# CP_Watsonville_South-Model.net
KiCad netlist of a schematic drawn in EAGLE
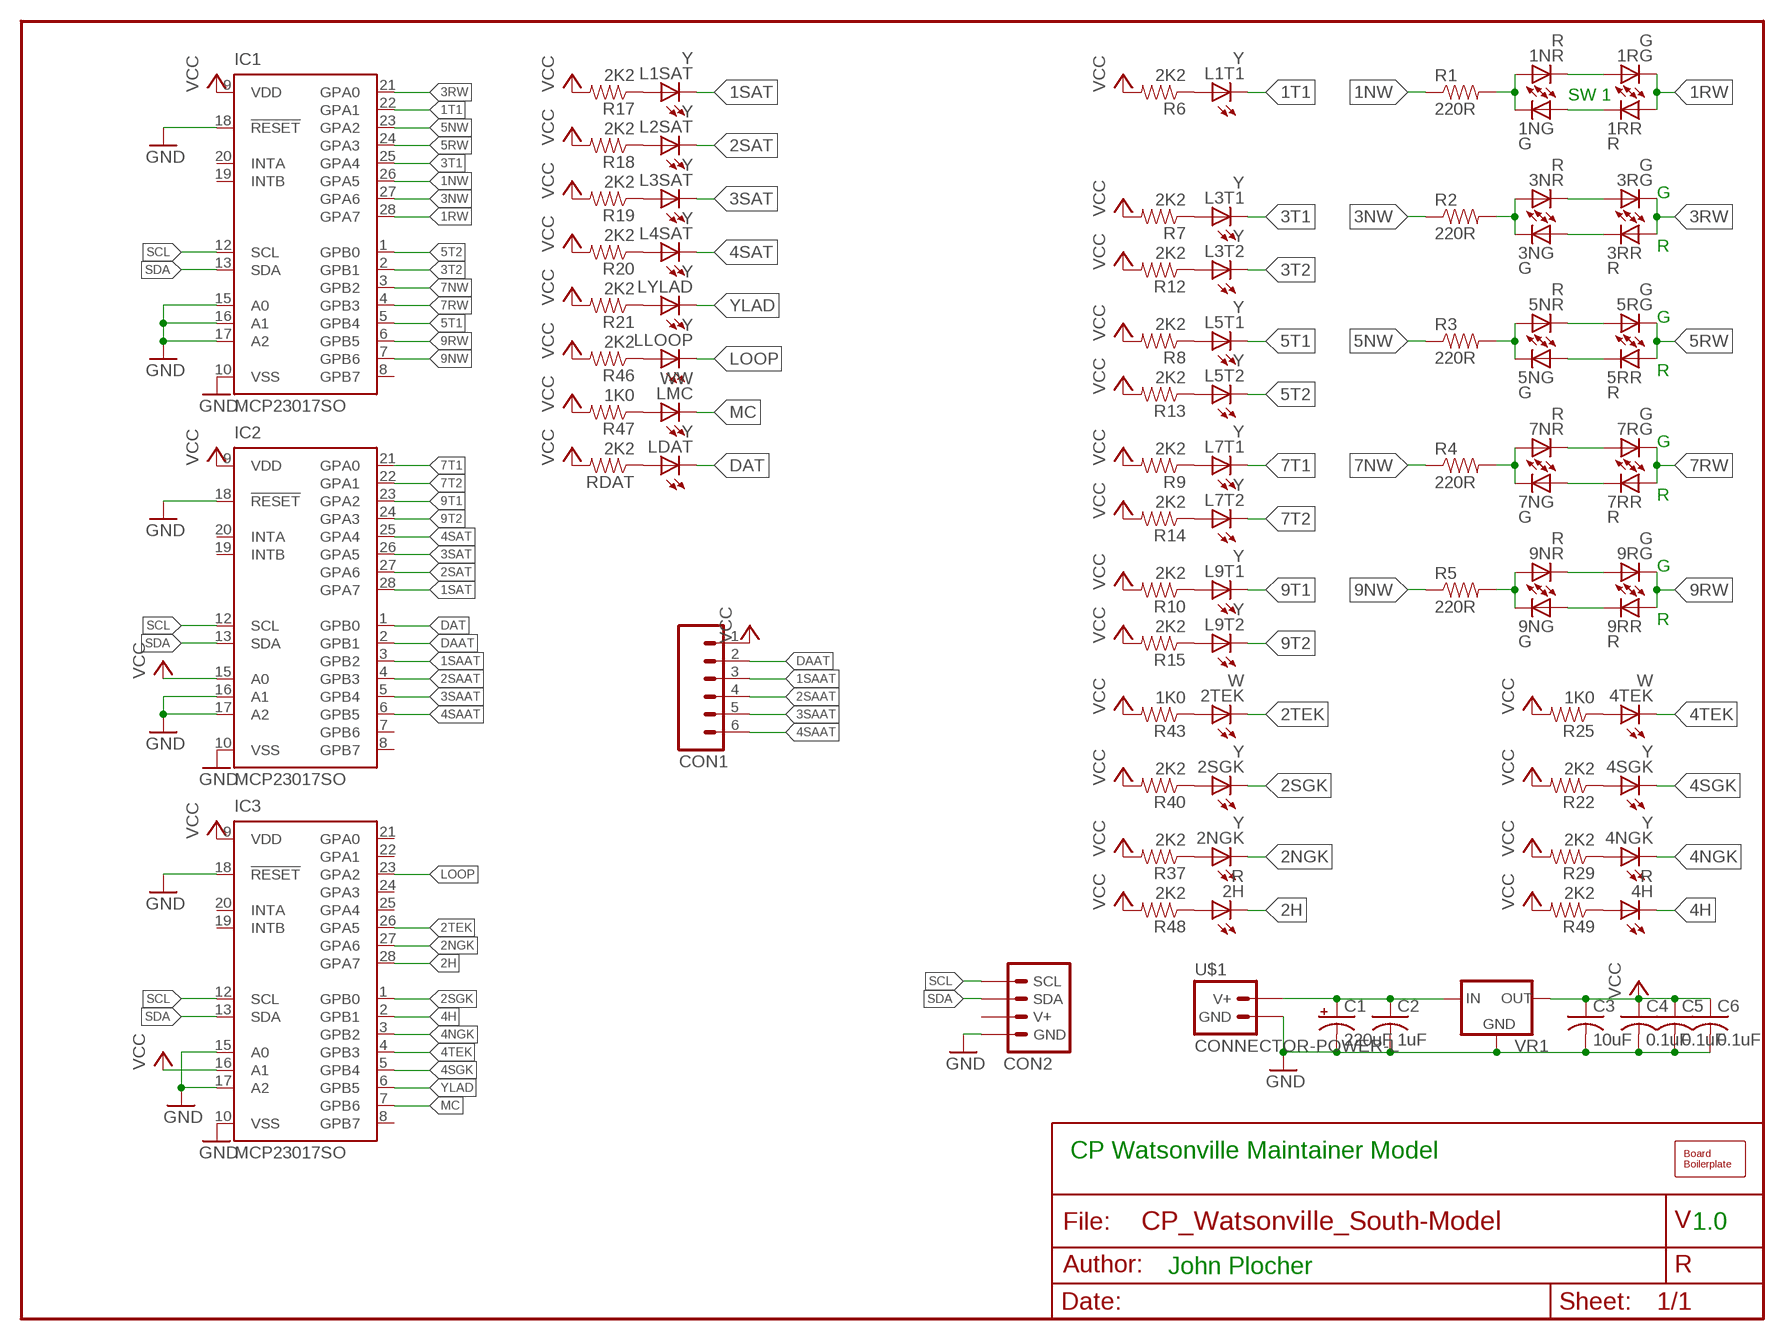
[diagram p0: schematic, sheet 1]

(export (version "E")
  (design (tool "Eeschema 10.0.6"))
  (components
    (comp (ref "1NG")
      (value "G")
      (footprint "eagle-import:0603-LED")
      (libsource (lib "eagle-import") (part "LED0603-LED"))
    )
    (comp (ref "1NR")
      (value "R")
      (footprint "eagle-import:0603-LED")
      (libsource (lib "eagle-import") (part "LED0603-LED"))
    )
    (comp (ref "1RG")
      (value "G")
      (footprint "eagle-import:0603-LED")
      (libsource (lib "eagle-import") (part "LED0603-LED"))
    )
    (comp (ref "1RR")
      (value "R")
      (footprint "eagle-import:0603-LED")
      (libsource (lib "eagle-import") (part "LED0603-LED"))
    )
    (comp (ref "2H")
      (value "R")
      (footprint "eagle-import:0603-LED")
      (libsource (lib "eagle-import") (part "LED0603-LED"))
    )
    (comp (ref "2NGK")
      (value "Y")
      (footprint "eagle-import:0603-LED")
      (libsource (lib "eagle-import") (part "LED0603-LED"))
    )
    (comp (ref "2SGK")
      (value "Y")
      (footprint "eagle-import:0603-LED")
      (libsource (lib "eagle-import") (part "LED0603-LED"))
    )
    (comp (ref "2TEK")
      (value "W")
      (footprint "eagle-import:0603-LED")
      (libsource (lib "eagle-import") (part "LED0603-LED"))
    )
    (comp (ref "3NG")
      (value "G")
      (footprint "eagle-import:0603-LED")
      (libsource (lib "eagle-import") (part "LED0603-LED"))
    )
    (comp (ref "3NR")
      (value "R")
      (footprint "eagle-import:0603-LED")
      (libsource (lib "eagle-import") (part "LED0603-LED"))
    )
    (comp (ref "3RG")
      (value "G")
      (footprint "eagle-import:0603-LED")
      (libsource (lib "eagle-import") (part "LED0603-LED"))
    )
    (comp (ref "3RR")
      (value "R")
      (footprint "eagle-import:0603-LED")
      (libsource (lib "eagle-import") (part "LED0603-LED"))
    )
    (comp (ref "4H")
      (value "R")
      (footprint "eagle-import:0603-LED")
      (libsource (lib "eagle-import") (part "LED0603-LED"))
    )
    (comp (ref "4NGK")
      (value "Y")
      (footprint "eagle-import:0603-LED")
      (libsource (lib "eagle-import") (part "LED0603-LED"))
    )
    (comp (ref "4SGK")
      (value "Y")
      (footprint "eagle-import:0603-LED")
      (libsource (lib "eagle-import") (part "LED0603-LED"))
    )
    (comp (ref "4TEK")
      (value "W")
      (footprint "eagle-import:0603-LED")
      (libsource (lib "eagle-import") (part "LED0603-LED"))
    )
    (comp (ref "5NG")
      (value "G")
      (footprint "eagle-import:0603-LED")
      (libsource (lib "eagle-import") (part "LED0603-LED"))
    )
    (comp (ref "5NR")
      (value "R")
      (footprint "eagle-import:0603-LED")
      (libsource (lib "eagle-import") (part "LED0603-LED"))
    )
    (comp (ref "5RG")
      (value "G")
      (footprint "eagle-import:0603-LED")
      (libsource (lib "eagle-import") (part "LED0603-LED"))
    )
    (comp (ref "5RR")
      (value "R")
      (footprint "eagle-import:0603-LED")
      (libsource (lib "eagle-import") (part "LED0603-LED"))
    )
    (comp (ref "7NG")
      (value "G")
      (footprint "eagle-import:0603-LED")
      (libsource (lib "eagle-import") (part "LED0603-LED"))
    )
    (comp (ref "7NR")
      (value "R")
      (footprint "eagle-import:0603-LED")
      (libsource (lib "eagle-import") (part "LED0603-LED"))
    )
    (comp (ref "7RG")
      (value "G")
      (footprint "eagle-import:0603-LED")
      (libsource (lib "eagle-import") (part "LED0603-LED"))
    )
    (comp (ref "7RR")
      (value "R")
      (footprint "eagle-import:0603-LED")
      (libsource (lib "eagle-import") (part "LED0603-LED"))
    )
    (comp (ref "9NG")
      (value "G")
      (footprint "eagle-import:0603-LED")
      (libsource (lib "eagle-import") (part "LED0603-LED"))
    )
    (comp (ref "9NR")
      (value "R")
      (footprint "eagle-import:0603-LED")
      (libsource (lib "eagle-import") (part "LED0603-LED"))
    )
    (comp (ref "9RG")
      (value "G")
      (footprint "eagle-import:0603-LED")
      (libsource (lib "eagle-import") (part "LED0603-LED"))
    )
    (comp (ref "9RR")
      (value "R")
      (footprint "eagle-import:0603-LED")
      (libsource (lib "eagle-import") (part "LED0603-LED"))
    )
    (comp (ref "BOARD1")
      (value "BOARD100X150")
      (footprint "eagle-import:BOARD-SEEED10X15")
      (libsource (lib "eagle-import") (part "BOARD100X150"))
    )
    (comp (ref "C1")
      (value "220uF")
      (footprint "eagle-import:0810-CAP")
      (libsource (lib "eagle-import") (part "CAP-POL0810"))
    )
    (comp (ref "C2")
      (value "1uF")
      (footprint "eagle-import:0603-CAP")
      (libsource (lib "eagle-import") (part "CAP0603"))
    )
    (comp (ref "C3")
      (value "10uF")
      (footprint "eagle-import:0603-CAP")
      (libsource (lib "eagle-import") (part "CAP0603"))
    )
    (comp (ref "C4")
      (value "0.1uF")
      (footprint "eagle-import:0603-CAP")
      (libsource (lib "eagle-import") (part "CAP0603"))
    )
    (comp (ref "C5")
      (value "0.1uF")
      (footprint "eagle-import:0603-CAP")
      (libsource (lib "eagle-import") (part "CAP0603"))
    )
    (comp (ref "C6")
      (value "0.1uF")
      (footprint "eagle-import:0603-CAP")
      (libsource (lib "eagle-import") (part "CAP0603"))
    )
    (comp (ref "CON1")
      (value "CONNECTOR-M06LOCK")
      (footprint "eagle-import:1X06_LOCK")
      (libsource (lib "eagle-import") (part "CONNECTOR-M06LOCK"))
    )
    (comp (ref "CON2")
      (value "CONNECTOR-I2CNOOUTLINE")
      (footprint "eagle-import:I2C-NOOUTLINE")
      (libsource (lib "eagle-import") (part "CONNECTOR-I2CNOOUTLINE"))
    )
    (comp (ref "IC1")
      (value "MCP23017SO")
      (footprint "eagle-import:SO28W")
      (fields (field (name "MF") "MICROCHIP") (field (name "MPN") "MCP23017-E/SO"))
      (libsource (lib "eagle-import") (part "MCP23017SO"))
    )
    (comp (ref "IC2")
      (value "MCP23017SO")
      (footprint "eagle-import:SO28W")
      (fields (field (name "MF") "MICROCHIP") (field (name "MPN") "MCP23017-E/SO"))
      (libsource (lib "eagle-import") (part "MCP23017SO"))
    )
    (comp (ref "IC3")
      (value "MCP23017SO")
      (footprint "eagle-import:SO28W")
      (fields (field (name "MF") "MICROCHIP") (field (name "MPN") "MCP23017-E/SO"))
      (libsource (lib "eagle-import") (part "MCP23017SO"))
    )
    (comp (ref "L1SAT")
      (value "Y")
      (footprint "eagle-import:0603-LED")
      (libsource (lib "eagle-import") (part "LED0603-LED"))
    )
    (comp (ref "L1T1")
      (value "Y")
      (footprint "eagle-import:0603-LED")
      (libsource (lib "eagle-import") (part "LED0603-LED"))
    )
    (comp (ref "L2SAT")
      (value "Y")
      (footprint "eagle-import:0603-LED")
      (libsource (lib "eagle-import") (part "LED0603-LED"))
    )
    (comp (ref "L3SAT")
      (value "Y")
      (footprint "eagle-import:0603-LED")
      (libsource (lib "eagle-import") (part "LED0603-LED"))
    )
    (comp (ref "L3T1")
      (value "Y")
      (footprint "eagle-import:0603-LED")
      (libsource (lib "eagle-import") (part "LED0603-LED"))
    )
    (comp (ref "L3T2")
      (value "Y")
      (footprint "eagle-import:0603-LED")
      (libsource (lib "eagle-import") (part "LED0603-LED"))
    )
    (comp (ref "L4SAT")
      (value "Y")
      (footprint "eagle-import:0603-LED")
      (libsource (lib "eagle-import") (part "LED0603-LED"))
    )
    (comp (ref "L5T1")
      (value "Y")
      (footprint "eagle-import:0603-LED")
      (libsource (lib "eagle-import") (part "LED0603-LED"))
    )
    (comp (ref "L5T2")
      (value "Y")
      (footprint "eagle-import:0603-LED")
      (libsource (lib "eagle-import") (part "LED0603-LED"))
    )
    (comp (ref "L7T1")
      (value "Y")
      (footprint "eagle-import:0603-LED")
      (libsource (lib "eagle-import") (part "LED0603-LED"))
    )
    (comp (ref "L7T2")
      (value "Y")
      (footprint "eagle-import:0603-LED")
      (libsource (lib "eagle-import") (part "LED0603-LED"))
    )
    (comp (ref "L9T1")
      (value "Y")
      (footprint "eagle-import:0603-LED")
      (libsource (lib "eagle-import") (part "LED0603-LED"))
    )
    (comp (ref "L9T2")
      (value "Y")
      (footprint "eagle-import:0603-LED")
      (libsource (lib "eagle-import") (part "LED0603-LED"))
    )
    (comp (ref "LDAT")
      (value "Y")
      (footprint "eagle-import:0603-LED")
      (libsource (lib "eagle-import") (part "LED0603-LED"))
    )
    (comp (ref "LLOOP")
      (value "Y")
      (footprint "eagle-import:0603-LED")
      (libsource (lib "eagle-import") (part "LED0603-LED"))
    )
    (comp (ref "LMC")
      (value "WW")
      (footprint "eagle-import:0603-LED")
      (libsource (lib "eagle-import") (part "LED0603-LED"))
    )
    (comp (ref "LYLAD")
      (value "Y")
      (footprint "eagle-import:0603-LED")
      (libsource (lib "eagle-import") (part "LED0603-LED"))
    )
    (comp (ref "R1")
      (value "220R")
      (footprint "eagle-import:0603-RES")
      (libsource (lib "eagle-import") (part "R0603-RES"))
    )
    (comp (ref "R2")
      (value "220R")
      (footprint "eagle-import:0603-RES")
      (libsource (lib "eagle-import") (part "R0603-RES"))
    )
    (comp (ref "R3")
      (value "220R")
      (footprint "eagle-import:0603-RES")
      (libsource (lib "eagle-import") (part "R0603-RES"))
    )
    (comp (ref "R4")
      (value "220R")
      (footprint "eagle-import:0603-RES")
      (libsource (lib "eagle-import") (part "R0603-RES"))
    )
    (comp (ref "R5")
      (value "220R")
      (footprint "eagle-import:0603-RES")
      (libsource (lib "eagle-import") (part "R0603-RES"))
    )
    (comp (ref "R6")
      (value "2K2")
      (footprint "eagle-import:0603-RES")
      (libsource (lib "eagle-import") (part "R0603-RES"))
    )
    (comp (ref "R7")
      (value "2K2")
      (footprint "eagle-import:0603-RES")
      (libsource (lib "eagle-import") (part "R0603-RES"))
    )
    (comp (ref "R8")
      (value "2K2")
      (footprint "eagle-import:0603-RES")
      (libsource (lib "eagle-import") (part "R0603-RES"))
    )
    (comp (ref "R9")
      (value "2K2")
      (footprint "eagle-import:0603-RES")
      (libsource (lib "eagle-import") (part "R0603-RES"))
    )
    (comp (ref "R10")
      (value "2K2")
      (footprint "eagle-import:0603-RES")
      (libsource (lib "eagle-import") (part "R0603-RES"))
    )
    (comp (ref "R12")
      (value "2K2")
      (footprint "eagle-import:0603-RES")
      (libsource (lib "eagle-import") (part "R0603-RES"))
    )
    (comp (ref "R13")
      (value "2K2")
      (footprint "eagle-import:0603-RES")
      (libsource (lib "eagle-import") (part "R0603-RES"))
    )
    (comp (ref "R14")
      (value "2K2")
      (footprint "eagle-import:0603-RES")
      (libsource (lib "eagle-import") (part "R0603-RES"))
    )
    (comp (ref "R15")
      (value "2K2")
      (footprint "eagle-import:0603-RES")
      (libsource (lib "eagle-import") (part "R0603-RES"))
    )
    (comp (ref "R17")
      (value "2K2")
      (footprint "eagle-import:0603-RES")
      (libsource (lib "eagle-import") (part "R0603-RES"))
    )
    (comp (ref "R18")
      (value "2K2")
      (footprint "eagle-import:0603-RES")
      (libsource (lib "eagle-import") (part "R0603-RES"))
    )
    (comp (ref "R19")
      (value "2K2")
      (footprint "eagle-import:0603-RES")
      (libsource (lib "eagle-import") (part "R0603-RES"))
    )
    (comp (ref "R20")
      (value "2K2")
      (footprint "eagle-import:0603-RES")
      (libsource (lib "eagle-import") (part "R0603-RES"))
    )
    (comp (ref "R21")
      (value "2K2")
      (footprint "eagle-import:0603-RES")
      (libsource (lib "eagle-import") (part "R0603-RES"))
    )
    (comp (ref "R22")
      (value "2K2")
      (footprint "eagle-import:0603-RES")
      (libsource (lib "eagle-import") (part "R0603-RES"))
    )
    (comp (ref "R25")
      (value "1K0")
      (footprint "eagle-import:0603-RES")
      (libsource (lib "eagle-import") (part "R0603-RES"))
    )
    (comp (ref "R29")
      (value "2K2")
      (footprint "eagle-import:0603-RES")
      (libsource (lib "eagle-import") (part "R0603-RES"))
    )
    (comp (ref "R37")
      (value "2K2")
      (footprint "eagle-import:0603-RES")
      (libsource (lib "eagle-import") (part "R0603-RES"))
    )
    (comp (ref "R40")
      (value "2K2")
      (footprint "eagle-import:0603-RES")
      (libsource (lib "eagle-import") (part "R0603-RES"))
    )
    (comp (ref "R43")
      (value "1K0")
      (footprint "eagle-import:0603-RES")
      (libsource (lib "eagle-import") (part "R0603-RES"))
    )
    (comp (ref "R46")
      (value "2K2")
      (footprint "eagle-import:0603-RES")
      (libsource (lib "eagle-import") (part "R0603-RES"))
    )
    (comp (ref "R47")
      (value "1K0")
      (footprint "eagle-import:0603-RES")
      (libsource (lib "eagle-import") (part "R0603-RES"))
    )
    (comp (ref "R48")
      (value "2K2")
      (footprint "eagle-import:0603-RES")
      (libsource (lib "eagle-import") (part "R0603-RES"))
    )
    (comp (ref "R49")
      (value "2K2")
      (footprint "eagle-import:0603-RES")
      (libsource (lib "eagle-import") (part "R0603-RES"))
    )
    (comp (ref "RDAT")
      (value "2K2")
      (footprint "eagle-import:0603-RES")
      (libsource (lib "eagle-import") (part "R0603-RES"))
    )
    (comp (ref "U$1")
      (value "CONNECTOR-POWER-L")
      (footprint "eagle-import:POWER-R2")
      (libsource (lib "eagle-import") (part "CONNECTOR-POWER-L"))
    )
    (comp (ref "VR1")
      (value "VREG-DPAK-5")
      (footprint "eagle-import:TO-252")
      (libsource (lib "eagle-import") (part "VREG-?-DPAK5"))
    )
  )
  (nets
    (net (code "1") (name "1NW") (class "Default")
      (node (ref "IC1") (pin "26") (pinfunction "GPA5_26") (pintype "bidirectional"))
      (node (ref "R1") (pin "1") (pinfunction "1_1") (pintype "passive"))
    )
    (net (code "2") (name "1RW") (class "Default")
      (node (ref "1RG") (pin "C") (pinfunction "C_C") (pintype "passive"))
      (node (ref "1RR") (pin "A") (pinfunction "A_A") (pintype "passive"))
      (node (ref "IC1") (pin "28") (pinfunction "GPA7_28") (pintype "bidirectional"))
    )
    (net (code "3") (name "1SAAT") (class "Default")
      (node (ref "CON1") (pin "3") (pinfunction "3_3") (pintype "passive"))
      (node (ref "IC2") (pin "3") (pinfunction "GPB2_3") (pintype "bidirectional"))
    )
    (net (code "4") (name "1SAT") (class "Default")
      (node (ref "IC2") (pin "28") (pinfunction "GPA7_28") (pintype "bidirectional"))
      (node (ref "L1SAT") (pin "C") (pinfunction "C_C") (pintype "passive"))
    )
    (net (code "5") (name "1T1") (class "Default")
      (node (ref "IC1") (pin "22") (pinfunction "GPA1_22") (pintype "bidirectional"))
      (node (ref "L1T1") (pin "C") (pinfunction "C_C") (pintype "passive"))
    )
    (net (code "6") (name "2H") (class "Default")
      (node (ref "2H") (pin "C") (pinfunction "C_C") (pintype "passive"))
      (node (ref "IC3") (pin "28") (pinfunction "GPA7_28") (pintype "bidirectional"))
    )
    (net (code "7") (name "2NGK") (class "Default")
      (node (ref "2NGK") (pin "C") (pinfunction "C_C") (pintype "passive"))
      (node (ref "IC3") (pin "27") (pinfunction "GPA6_27") (pintype "bidirectional"))
    )
    (net (code "8") (name "2SAAT") (class "Default")
      (node (ref "CON1") (pin "4") (pinfunction "4_4") (pintype "passive"))
      (node (ref "IC2") (pin "4") (pinfunction "GPB3_4") (pintype "bidirectional"))
    )
    (net (code "9") (name "2SAT") (class "Default")
      (node (ref "IC2") (pin "27") (pinfunction "GPA6_27") (pintype "bidirectional"))
      (node (ref "L2SAT") (pin "C") (pinfunction "C_C") (pintype "passive"))
    )
    (net (code "10") (name "2SGK") (class "Default")
      (node (ref "2SGK") (pin "C") (pinfunction "C_C") (pintype "passive"))
      (node (ref "IC3") (pin "1") (pinfunction "GPB0_1") (pintype "bidirectional"))
    )
    (net (code "11") (name "2TEK") (class "Default")
      (node (ref "2TEK") (pin "C") (pinfunction "C_C") (pintype "passive"))
      (node (ref "IC3") (pin "26") (pinfunction "GPA5_26") (pintype "bidirectional"))
    )
    (net (code "12") (name "3NW") (class "Default")
      (node (ref "IC1") (pin "27") (pinfunction "GPA6_27") (pintype "bidirectional"))
      (node (ref "R2") (pin "1") (pinfunction "1_1") (pintype "passive"))
    )
    (net (code "13") (name "3RW") (class "Default")
      (node (ref "3RG") (pin "C") (pinfunction "C_C") (pintype "passive"))
      (node (ref "3RR") (pin "A") (pinfunction "A_A") (pintype "passive"))
      (node (ref "IC1") (pin "21") (pinfunction "GPA0_21") (pintype "bidirectional"))
    )
    (net (code "14") (name "3SAAT") (class "Default")
      (node (ref "CON1") (pin "5") (pinfunction "5_5") (pintype "passive"))
      (node (ref "IC2") (pin "5") (pinfunction "GPB4_5") (pintype "bidirectional"))
    )
    (net (code "15") (name "3SAT") (class "Default")
      (node (ref "IC2") (pin "26") (pinfunction "GPA5_26") (pintype "bidirectional"))
      (node (ref "L3SAT") (pin "C") (pinfunction "C_C") (pintype "passive"))
    )
    (net (code "16") (name "3T1") (class "Default")
      (node (ref "IC1") (pin "25") (pinfunction "GPA4_25") (pintype "bidirectional"))
      (node (ref "L3T1") (pin "C") (pinfunction "C_C") (pintype "passive"))
    )
    (net (code "17") (name "3T2") (class "Default")
      (node (ref "IC1") (pin "2") (pinfunction "GPB1_2") (pintype "bidirectional"))
      (node (ref "L3T2") (pin "C") (pinfunction "C_C") (pintype "passive"))
    )
    (net (code "18") (name "4H") (class "Default")
      (node (ref "4H") (pin "C") (pinfunction "C_C") (pintype "passive"))
      (node (ref "IC3") (pin "2") (pinfunction "GPB1_2") (pintype "bidirectional"))
    )
    (net (code "19") (name "4NGK") (class "Default")
      (node (ref "4NGK") (pin "C") (pinfunction "C_C") (pintype "passive"))
      (node (ref "IC3") (pin "3") (pinfunction "GPB2_3") (pintype "bidirectional"))
    )
    (net (code "20") (name "4SAAT") (class "Default")
      (node (ref "CON1") (pin "6") (pinfunction "6_6") (pintype "passive"))
      (node (ref "IC2") (pin "6") (pinfunction "GPB5_6") (pintype "bidirectional"))
    )
    (net (code "21") (name "4SAT") (class "Default")
      (node (ref "IC2") (pin "25") (pinfunction "GPA4_25") (pintype "bidirectional"))
      (node (ref "L4SAT") (pin "C") (pinfunction "C_C") (pintype "passive"))
    )
    (net (code "22") (name "4SGK") (class "Default")
      (node (ref "4SGK") (pin "C") (pinfunction "C_C") (pintype "passive"))
      (node (ref "IC3") (pin "5") (pinfunction "GPB4_5") (pintype "bidirectional"))
    )
    (net (code "23") (name "4TEK") (class "Default")
      (node (ref "4TEK") (pin "C") (pinfunction "C_C") (pintype "passive"))
      (node (ref "IC3") (pin "4") (pinfunction "GPB3_4") (pintype "bidirectional"))
    )
    (net (code "24") (name "5NW") (class "Default")
      (node (ref "IC1") (pin "23") (pinfunction "GPA2_23") (pintype "bidirectional"))
      (node (ref "R3") (pin "1") (pinfunction "1_1") (pintype "passive"))
    )
    (net (code "25") (name "5RW") (class "Default")
      (node (ref "5RG") (pin "C") (pinfunction "C_C") (pintype "passive"))
      (node (ref "5RR") (pin "A") (pinfunction "A_A") (pintype "passive"))
      (node (ref "IC1") (pin "24") (pinfunction "GPA3_24") (pintype "bidirectional"))
    )
    (net (code "26") (name "5T1") (class "Default")
      (node (ref "IC1") (pin "5") (pinfunction "GPB4_5") (pintype "bidirectional"))
      (node (ref "L5T1") (pin "C") (pinfunction "C_C") (pintype "passive"))
    )
    (net (code "27") (name "5T2") (class "Default")
      (node (ref "IC1") (pin "1") (pinfunction "GPB0_1") (pintype "bidirectional"))
      (node (ref "L5T2") (pin "C") (pinfunction "C_C") (pintype "passive"))
    )
    (net (code "28") (name "7NW") (class "Default")
      (node (ref "IC1") (pin "3") (pinfunction "GPB2_3") (pintype "bidirectional"))
      (node (ref "R4") (pin "1") (pinfunction "1_1") (pintype "passive"))
    )
    (net (code "29") (name "7RW") (class "Default")
      (node (ref "7RG") (pin "C") (pinfunction "C_C") (pintype "passive"))
      (node (ref "7RR") (pin "A") (pinfunction "A_A") (pintype "passive"))
      (node (ref "IC1") (pin "4") (pinfunction "GPB3_4") (pintype "bidirectional"))
    )
    (net (code "30") (name "7T1") (class "Default")
      (node (ref "IC2") (pin "21") (pinfunction "GPA0_21") (pintype "bidirectional"))
      (node (ref "L7T1") (pin "C") (pinfunction "C_C") (pintype "passive"))
    )
    (net (code "31") (name "7T2") (class "Default")
      (node (ref "IC2") (pin "22") (pinfunction "GPA1_22") (pintype "bidirectional"))
      (node (ref "L7T2") (pin "C") (pinfunction "C_C") (pintype "passive"))
    )
    (net (code "32") (name "9NW") (class "Default")
      (node (ref "IC1") (pin "7") (pinfunction "GPB6_7") (pintype "bidirectional"))
      (node (ref "R5") (pin "1") (pinfunction "1_1") (pintype "passive"))
    )
    (net (code "33") (name "9RW") (class "Default")
      (node (ref "9RG") (pin "C") (pinfunction "C_C") (pintype "passive"))
      (node (ref "9RR") (pin "A") (pinfunction "A_A") (pintype "passive"))
      (node (ref "IC1") (pin "6") (pinfunction "GPB5_6") (pintype "bidirectional"))
    )
    (net (code "34") (name "9T1") (class "Default")
      (node (ref "IC2") (pin "23") (pinfunction "GPA2_23") (pintype "bidirectional"))
      (node (ref "L9T1") (pin "C") (pinfunction "C_C") (pintype "passive"))
    )
    (net (code "35") (name "9T2") (class "Default")
      (node (ref "IC2") (pin "24") (pinfunction "GPA3_24") (pintype "bidirectional"))
      (node (ref "L9T2") (pin "C") (pinfunction "C_C") (pintype "passive"))
    )
    (net (code "36") (name "DAAT") (class "Default")
      (node (ref "CON1") (pin "2") (pinfunction "2_2") (pintype "passive"))
      (node (ref "IC2") (pin "2") (pinfunction "GPB1_2") (pintype "bidirectional"))
    )
    (net (code "37") (name "DAT") (class "Default")
      (node (ref "IC2") (pin "1") (pinfunction "GPB0_1") (pintype "bidirectional"))
      (node (ref "LDAT") (pin "C") (pinfunction "C_C") (pintype "passive"))
    )
    (net (code "38") (name "GND") (class "Default")
      (node (ref "C1") (pin "-") (pinfunction "-_-") (pintype "passive"))
      (node (ref "C2") (pin "2") (pinfunction "2_2") (pintype "passive"))
      (node (ref "C3") (pin "2") (pinfunction "2_2") (pintype "passive"))
      (node (ref "C4") (pin "2") (pinfunction "2_2") (pintype "passive"))
      (node (ref "C5") (pin "2") (pinfunction "2_2") (pintype "passive"))
      (node (ref "C6") (pin "2") (pinfunction "2_2") (pintype "passive"))
      (node (ref "CON2") (pin "GND") (pinfunction "GND_GND") (pintype "passive"))
      (node (ref "IC1") (pin "10") (pinfunction "VSS_10") (pintype "power_in"))
      (node (ref "IC1") (pin "15") (pinfunction "A0_15") (pintype "input"))
      (node (ref "IC1") (pin "16") (pinfunction "A1_16") (pintype "input"))
      (node (ref "IC1") (pin "17") (pinfunction "A2_17") (pintype "input"))
      (node (ref "IC1") (pin "18") (pinfunction "~{RESET}_18") (pintype "input"))
      (node (ref "IC2") (pin "10") (pinfunction "VSS_10") (pintype "power_in"))
      (node (ref "IC2") (pin "16") (pinfunction "A1_16") (pintype "input"))
      (node (ref "IC2") (pin "17") (pinfunction "A2_17") (pintype "input"))
      (node (ref "IC2") (pin "18") (pinfunction "~{RESET}_18") (pintype "input"))
      (node (ref "IC3") (pin "10") (pinfunction "VSS_10") (pintype "power_in"))
      (node (ref "IC3") (pin "15") (pinfunction "A0_15") (pintype "input"))
      (node (ref "IC3") (pin "17") (pinfunction "A2_17") (pintype "input"))
      (node (ref "IC3") (pin "18") (pinfunction "~{RESET}_18") (pintype "input"))
      (node (ref "U$1") (pin "GND") (pinfunction "GND_GND") (pintype "passive"))
      (node (ref "U$1") (pin "GND@1") (pinfunction "GND_GND@1") (pintype "passive"))
      (node (ref "U$1") (pin "GND@2") (pinfunction "GND_GND@2") (pintype "passive"))
      (node (ref "U$1") (pin "GND@3") (pinfunction "GND_GND@3") (pintype "passive"))
      (node (ref "VR1") (pin "2") (pinfunction "GND_2") (pintype "input"))
    )
    (net (code "39") (name "LOOP") (class "Default")
      (node (ref "IC3") (pin "23") (pinfunction "GPA2_23") (pintype "bidirectional"))
      (node (ref "LLOOP") (pin "C") (pinfunction "C_C") (pintype "passive"))
    )
    (net (code "40") (name "MC") (class "Default")
      (node (ref "IC3") (pin "7") (pinfunction "GPB6_7") (pintype "bidirectional"))
      (node (ref "LMC") (pin "C") (pinfunction "C_C") (pintype "passive"))
    )
    (net (code "41") (name "Net-(1NG-PadA)") (class "Default")
      (node (ref "1NG") (pin "A") (pinfunction "A_A") (pintype "passive"))
      (node (ref "1RR") (pin "C") (pinfunction "C_C") (pintype "passive"))
    )
    (net (code "42") (name "Net-(1NG-PadC)") (class "Default")
      (node (ref "1NG") (pin "C") (pinfunction "C_C") (pintype "passive"))
      (node (ref "1NR") (pin "A") (pinfunction "A_A") (pintype "passive"))
      (node (ref "R1") (pin "2") (pinfunction "2_2") (pintype "passive"))
    )
    (net (code "43") (name "Net-(1NR-PadC)") (class "Default")
      (node (ref "1NR") (pin "C") (pinfunction "C_C") (pintype "passive"))
      (node (ref "1RG") (pin "A") (pinfunction "A_A") (pintype "passive"))
    )
    (net (code "44") (name "Net-(2H-PadA)") (class "Default")
      (node (ref "2H") (pin "A") (pinfunction "A_A") (pintype "passive"))
      (node (ref "R48") (pin "1") (pinfunction "1_1") (pintype "passive"))
    )
    (net (code "45") (name "Net-(2NGK-PadA)") (class "Default")
      (node (ref "2NGK") (pin "A") (pinfunction "A_A") (pintype "passive"))
      (node (ref "R37") (pin "1") (pinfunction "1_1") (pintype "passive"))
    )
    (net (code "46") (name "Net-(2SGK-PadA)") (class "Default")
      (node (ref "2SGK") (pin "A") (pinfunction "A_A") (pintype "passive"))
      (node (ref "R40") (pin "1") (pinfunction "1_1") (pintype "passive"))
    )
    (net (code "47") (name "Net-(2TEK-PadA)") (class "Default")
      (node (ref "2TEK") (pin "A") (pinfunction "A_A") (pintype "passive"))
      (node (ref "R43") (pin "1") (pinfunction "1_1") (pintype "passive"))
    )
    (net (code "48") (name "Net-(3NG-PadA)") (class "Default")
      (node (ref "3NG") (pin "A") (pinfunction "A_A") (pintype "passive"))
      (node (ref "3RR") (pin "C") (pinfunction "C_C") (pintype "passive"))
    )
    (net (code "49") (name "Net-(3NG-PadC)") (class "Default")
      (node (ref "3NG") (pin "C") (pinfunction "C_C") (pintype "passive"))
      (node (ref "3NR") (pin "A") (pinfunction "A_A") (pintype "passive"))
      (node (ref "R2") (pin "2") (pinfunction "2_2") (pintype "passive"))
    )
    (net (code "50") (name "Net-(3NR-PadC)") (class "Default")
      (node (ref "3NR") (pin "C") (pinfunction "C_C") (pintype "passive"))
      (node (ref "3RG") (pin "A") (pinfunction "A_A") (pintype "passive"))
    )
    (net (code "51") (name "Net-(4H-PadA)") (class "Default")
      (node (ref "4H") (pin "A") (pinfunction "A_A") (pintype "passive"))
      (node (ref "R49") (pin "1") (pinfunction "1_1") (pintype "passive"))
    )
    (net (code "52") (name "Net-(4NGK-PadA)") (class "Default")
      (node (ref "4NGK") (pin "A") (pinfunction "A_A") (pintype "passive"))
      (node (ref "R29") (pin "1") (pinfunction "1_1") (pintype "passive"))
    )
    (net (code "53") (name "Net-(4SGK-PadA)") (class "Default")
      (node (ref "4SGK") (pin "A") (pinfunction "A_A") (pintype "passive"))
      (node (ref "R22") (pin "1") (pinfunction "1_1") (pintype "passive"))
    )
    (net (code "54") (name "Net-(4TEK-PadA)") (class "Default")
      (node (ref "4TEK") (pin "A") (pinfunction "A_A") (pintype "passive"))
      (node (ref "R25") (pin "1") (pinfunction "1_1") (pintype "passive"))
    )
    (net (code "55") (name "Net-(5NG-PadA)") (class "Default")
      (node (ref "5NG") (pin "A") (pinfunction "A_A") (pintype "passive"))
      (node (ref "5RR") (pin "C") (pinfunction "C_C") (pintype "passive"))
    )
    (net (code "56") (name "Net-(5NG-PadC)") (class "Default")
      (node (ref "5NG") (pin "C") (pinfunction "C_C") (pintype "passive"))
      (node (ref "5NR") (pin "A") (pinfunction "A_A") (pintype "passive"))
      (node (ref "R3") (pin "2") (pinfunction "2_2") (pintype "passive"))
    )
    (net (code "57") (name "Net-(5NR-PadC)") (class "Default")
      (node (ref "5NR") (pin "C") (pinfunction "C_C") (pintype "passive"))
      (node (ref "5RG") (pin "A") (pinfunction "A_A") (pintype "passive"))
    )
    (net (code "58") (name "Net-(7NG-PadA)") (class "Default")
      (node (ref "7NG") (pin "A") (pinfunction "A_A") (pintype "passive"))
      (node (ref "7RR") (pin "C") (pinfunction "C_C") (pintype "passive"))
    )
    (net (code "59") (name "Net-(7NG-PadC)") (class "Default")
      (node (ref "7NG") (pin "C") (pinfunction "C_C") (pintype "passive"))
      (node (ref "7NR") (pin "A") (pinfunction "A_A") (pintype "passive"))
      (node (ref "R4") (pin "2") (pinfunction "2_2") (pintype "passive"))
    )
    (net (code "60") (name "Net-(7NR-PadC)") (class "Default")
      (node (ref "7NR") (pin "C") (pinfunction "C_C") (pintype "passive"))
      (node (ref "7RG") (pin "A") (pinfunction "A_A") (pintype "passive"))
    )
    (net (code "61") (name "Net-(9NG-PadA)") (class "Default")
      (node (ref "9NG") (pin "A") (pinfunction "A_A") (pintype "passive"))
      (node (ref "9RR") (pin "C") (pinfunction "C_C") (pintype "passive"))
    )
    (net (code "62") (name "Net-(9NG-PadC)") (class "Default")
      (node (ref "9NG") (pin "C") (pinfunction "C_C") (pintype "passive"))
      (node (ref "9NR") (pin "A") (pinfunction "A_A") (pintype "passive"))
      (node (ref "R5") (pin "2") (pinfunction "2_2") (pintype "passive"))
    )
    (net (code "63") (name "Net-(9NR-PadC)") (class "Default")
      (node (ref "9NR") (pin "C") (pinfunction "C_C") (pintype "passive"))
      (node (ref "9RG") (pin "A") (pinfunction "A_A") (pintype "passive"))
    )
    (net (code "64") (name "Net-(L1SAT-PadA)") (class "Default")
      (node (ref "L1SAT") (pin "A") (pinfunction "A_A") (pintype "passive"))
      (node (ref "R17") (pin "1") (pinfunction "1_1") (pintype "passive"))
    )
    (net (code "65") (name "Net-(L1T1-PadA)") (class "Default")
      (node (ref "L1T1") (pin "A") (pinfunction "A_A") (pintype "passive"))
      (node (ref "R6") (pin "1") (pinfunction "1_1") (pintype "passive"))
    )
    (net (code "66") (name "Net-(L2SAT-PadA)") (class "Default")
      (node (ref "L2SAT") (pin "A") (pinfunction "A_A") (pintype "passive"))
      (node (ref "R18") (pin "1") (pinfunction "1_1") (pintype "passive"))
    )
    (net (code "67") (name "Net-(L3SAT-PadA)") (class "Default")
      (node (ref "L3SAT") (pin "A") (pinfunction "A_A") (pintype "passive"))
      (node (ref "R19") (pin "1") (pinfunction "1_1") (pintype "passive"))
    )
    (net (code "68") (name "Net-(L3T1-PadA)") (class "Default")
      (node (ref "L3T1") (pin "A") (pinfunction "A_A") (pintype "passive"))
      (node (ref "R7") (pin "1") (pinfunction "1_1") (pintype "passive"))
    )
    (net (code "69") (name "Net-(L3T2-PadA)") (class "Default")
      (node (ref "L3T2") (pin "A") (pinfunction "A_A") (pintype "passive"))
      (node (ref "R12") (pin "1") (pinfunction "1_1") (pintype "passive"))
    )
    (net (code "70") (name "Net-(L4SAT-PadA)") (class "Default")
      (node (ref "L4SAT") (pin "A") (pinfunction "A_A") (pintype "passive"))
      (node (ref "R20") (pin "1") (pinfunction "1_1") (pintype "passive"))
    )
    (net (code "71") (name "Net-(L5T1-PadA)") (class "Default")
      (node (ref "L5T1") (pin "A") (pinfunction "A_A") (pintype "passive"))
      (node (ref "R8") (pin "1") (pinfunction "1_1") (pintype "passive"))
    )
    (net (code "72") (name "Net-(L5T2-PadA)") (class "Default")
      (node (ref "L5T2") (pin "A") (pinfunction "A_A") (pintype "passive"))
      (node (ref "R13") (pin "1") (pinfunction "1_1") (pintype "passive"))
    )
    (net (code "73") (name "Net-(L7T1-PadA)") (class "Default")
      (node (ref "L7T1") (pin "A") (pinfunction "A_A") (pintype "passive"))
      (node (ref "R9") (pin "1") (pinfunction "1_1") (pintype "passive"))
    )
    (net (code "74") (name "Net-(L7T2-PadA)") (class "Default")
      (node (ref "L7T2") (pin "A") (pinfunction "A_A") (pintype "passive"))
      (node (ref "R14") (pin "1") (pinfunction "1_1") (pintype "passive"))
    )
    (net (code "75") (name "Net-(L9T1-PadA)") (class "Default")
      (node (ref "L9T1") (pin "A") (pinfunction "A_A") (pintype "passive"))
      (node (ref "R10") (pin "1") (pinfunction "1_1") (pintype "passive"))
    )
    (net (code "76") (name "Net-(L9T2-PadA)") (class "Default")
      (node (ref "L9T2") (pin "A") (pinfunction "A_A") (pintype "passive"))
      (node (ref "R15") (pin "1") (pinfunction "1_1") (pintype "passive"))
    )
    (net (code "77") (name "Net-(LDAT-PadA)") (class "Default")
      (node (ref "LDAT") (pin "A") (pinfunction "A_A") (pintype "passive"))
      (node (ref "RDAT") (pin "1") (pinfunction "1_1") (pintype "passive"))
    )
    (net (code "78") (name "Net-(LLOOP-PadA)") (class "Default")
      (node (ref "LLOOP") (pin "A") (pinfunction "A_A") (pintype "passive"))
      (node (ref "R46") (pin "1") (pinfunction "1_1") (pintype "passive"))
    )
    (net (code "79") (name "Net-(LMC-PadA)") (class "Default")
      (node (ref "LMC") (pin "A") (pinfunction "A_A") (pintype "passive"))
      (node (ref "R47") (pin "1") (pinfunction "1_1") (pintype "passive"))
    )
    (net (code "80") (name "Net-(LYLAD-PadA)") (class "Default")
      (node (ref "LYLAD") (pin "A") (pinfunction "A_A") (pintype "passive"))
      (node (ref "R21") (pin "1") (pinfunction "1_1") (pintype "passive"))
    )
    (net (code "81") (name "Net-(VR1-IN)") (class "Default")
      (node (ref "C1") (pin "+") (pinfunction "+_+") (pintype "passive"))
      (node (ref "C2") (pin "1") (pinfunction "1_1") (pintype "passive"))
      (node (ref "U$1") (pin "V+") (pinfunction "V+_V+") (pintype "passive"))
      (node (ref "U$1") (pin "V+@1") (pinfunction "V+_V+@1") (pintype "passive"))
      (node (ref "U$1") (pin "V+@2") (pinfunction "V+_V+@2") (pintype "passive"))
      (node (ref "U$1") (pin "V+@3") (pinfunction "V+_V+@3") (pintype "passive"))
      (node (ref "VR1") (pin "1") (pinfunction "IN_1") (pintype "input"))
    )
    (net (code "82") (name "SCL") (class "Default")
      (node (ref "CON2") (pin "SCL") (pinfunction "SCL_SCL") (pintype "passive"))
      (node (ref "IC1") (pin "12") (pinfunction "SCL_12") (pintype "input"))
      (node (ref "IC2") (pin "12") (pinfunction "SCL_12") (pintype "input"))
      (node (ref "IC3") (pin "12") (pinfunction "SCL_12") (pintype "input"))
    )
    (net (code "83") (name "SDA") (class "Default")
      (node (ref "CON2") (pin "SDA") (pinfunction "SDA_SDA") (pintype "passive"))
      (node (ref "IC1") (pin "13") (pinfunction "SDA_13") (pintype "bidirectional"))
      (node (ref "IC2") (pin "13") (pinfunction "SDA_13") (pintype "bidirectional"))
      (node (ref "IC3") (pin "13") (pinfunction "SDA_13") (pintype "bidirectional"))
    )
    (net (code "84") (name "VCC") (class "Default")
      (node (ref "C3") (pin "1") (pinfunction "1_1") (pintype "passive"))
      (node (ref "C4") (pin "1") (pinfunction "1_1") (pintype "passive"))
      (node (ref "C5") (pin "1") (pinfunction "1_1") (pintype "passive"))
      (node (ref "C6") (pin "1") (pinfunction "1_1") (pintype "passive"))
      (node (ref "CON1") (pin "1") (pinfunction "1_1") (pintype "passive"))
      (node (ref "IC1") (pin "9") (pinfunction "VDD_9") (pintype "power_in"))
      (node (ref "IC2") (pin "15") (pinfunction "A0_15") (pintype "input"))
      (node (ref "IC2") (pin "9") (pinfunction "VDD_9") (pintype "power_in"))
      (node (ref "IC3") (pin "16") (pinfunction "A1_16") (pintype "input"))
      (node (ref "IC3") (pin "9") (pinfunction "VDD_9") (pintype "power_in"))
      (node (ref "R10") (pin "2") (pinfunction "2_2") (pintype "passive"))
      (node (ref "R12") (pin "2") (pinfunction "2_2") (pintype "passive"))
      (node (ref "R13") (pin "2") (pinfunction "2_2") (pintype "passive"))
      (node (ref "R14") (pin "2") (pinfunction "2_2") (pintype "passive"))
      (node (ref "R15") (pin "2") (pinfunction "2_2") (pintype "passive"))
      (node (ref "R17") (pin "2") (pinfunction "2_2") (pintype "passive"))
      (node (ref "R18") (pin "2") (pinfunction "2_2") (pintype "passive"))
      (node (ref "R19") (pin "2") (pinfunction "2_2") (pintype "passive"))
      (node (ref "R20") (pin "2") (pinfunction "2_2") (pintype "passive"))
      (node (ref "R21") (pin "2") (pinfunction "2_2") (pintype "passive"))
      (node (ref "R22") (pin "2") (pinfunction "2_2") (pintype "passive"))
      (node (ref "R25") (pin "2") (pinfunction "2_2") (pintype "passive"))
      (node (ref "R29") (pin "2") (pinfunction "2_2") (pintype "passive"))
      (node (ref "R37") (pin "2") (pinfunction "2_2") (pintype "passive"))
      (node (ref "R40") (pin "2") (pinfunction "2_2") (pintype "passive"))
      (node (ref "R43") (pin "2") (pinfunction "2_2") (pintype "passive"))
      (node (ref "R46") (pin "2") (pinfunction "2_2") (pintype "passive"))
      (node (ref "R47") (pin "2") (pinfunction "2_2") (pintype "passive"))
      (node (ref "R48") (pin "2") (pinfunction "2_2") (pintype "passive"))
      (node (ref "R49") (pin "2") (pinfunction "2_2") (pintype "passive"))
      (node (ref "R6") (pin "2") (pinfunction "2_2") (pintype "passive"))
      (node (ref "R7") (pin "2") (pinfunction "2_2") (pintype "passive"))
      (node (ref "R8") (pin "2") (pinfunction "2_2") (pintype "passive"))
      (node (ref "R9") (pin "2") (pinfunction "2_2") (pintype "passive"))
      (node (ref "RDAT") (pin "2") (pinfunction "2_2") (pintype "passive"))
      (node (ref "VR1") (pin "3") (pinfunction "OUT_3") (pintype "output"))
    )
    (net (code "85") (name "YLAD") (class "Default")
      (node (ref "IC3") (pin "6") (pinfunction "GPB5_6") (pintype "bidirectional"))
      (node (ref "LYLAD") (pin "C") (pinfunction "C_C") (pintype "passive"))
    )
    (net (code "86") (name "unconnected-(CON2-PadV+)") (class "Default")
      (node (ref "CON2") (pin "V+") (pinfunction "V+_V+") (pintype "passive"))
    )
    (net (code "87") (name "unconnected-(IC1-GPB7-Pad8)") (class "Default")
      (node (ref "IC1") (pin "8") (pinfunction "GPB7_8") (pintype "bidirectional"))
    )
    (net (code "88") (name "unconnected-(IC1-INTA-Pad20)") (class "Default")
      (node (ref "IC1") (pin "20") (pinfunction "INTA_20") (pintype "output"))
    )
    (net (code "89") (name "unconnected-(IC1-INTB-Pad19)") (class "Default")
      (node (ref "IC1") (pin "19") (pinfunction "INTB_19") (pintype "output"))
    )
    (net (code "90") (name "unconnected-(IC2-GPB6-Pad7)") (class "Default")
      (node (ref "IC2") (pin "7") (pinfunction "GPB6_7") (pintype "bidirectional"))
    )
    (net (code "91") (name "unconnected-(IC2-GPB7-Pad8)") (class "Default")
      (node (ref "IC2") (pin "8") (pinfunction "GPB7_8") (pintype "bidirectional"))
    )
    (net (code "92") (name "unconnected-(IC2-INTA-Pad20)") (class "Default")
      (node (ref "IC2") (pin "20") (pinfunction "INTA_20") (pintype "output"))
    )
    (net (code "93") (name "unconnected-(IC2-INTB-Pad19)") (class "Default")
      (node (ref "IC2") (pin "19") (pinfunction "INTB_19") (pintype "output"))
    )
    (net (code "94") (name "unconnected-(IC3-GPA0-Pad21)") (class "Default")
      (node (ref "IC3") (pin "21") (pinfunction "GPA0_21") (pintype "bidirectional"))
    )
    (net (code "95") (name "unconnected-(IC3-GPA1-Pad22)") (class "Default")
      (node (ref "IC3") (pin "22") (pinfunction "GPA1_22") (pintype "bidirectional"))
    )
    (net (code "96") (name "unconnected-(IC3-GPA3-Pad24)") (class "Default")
      (node (ref "IC3") (pin "24") (pinfunction "GPA3_24") (pintype "bidirectional"))
    )
    (net (code "97") (name "unconnected-(IC3-GPA4-Pad25)") (class "Default")
      (node (ref "IC3") (pin "25") (pinfunction "GPA4_25") (pintype "bidirectional"))
    )
    (net (code "98") (name "unconnected-(IC3-GPB7-Pad8)") (class "Default")
      (node (ref "IC3") (pin "8") (pinfunction "GPB7_8") (pintype "bidirectional"))
    )
    (net (code "99") (name "unconnected-(IC3-INTA-Pad20)") (class "Default")
      (node (ref "IC3") (pin "20") (pinfunction "INTA_20") (pintype "output"))
    )
    (net (code "100") (name "unconnected-(IC3-INTB-Pad19)") (class "Default")
      (node (ref "IC3") (pin "19") (pinfunction "INTB_19") (pintype "output"))
    )
  )
)
